# MCU.net
KiCad netlist of a schematic drawn in Altium Designer
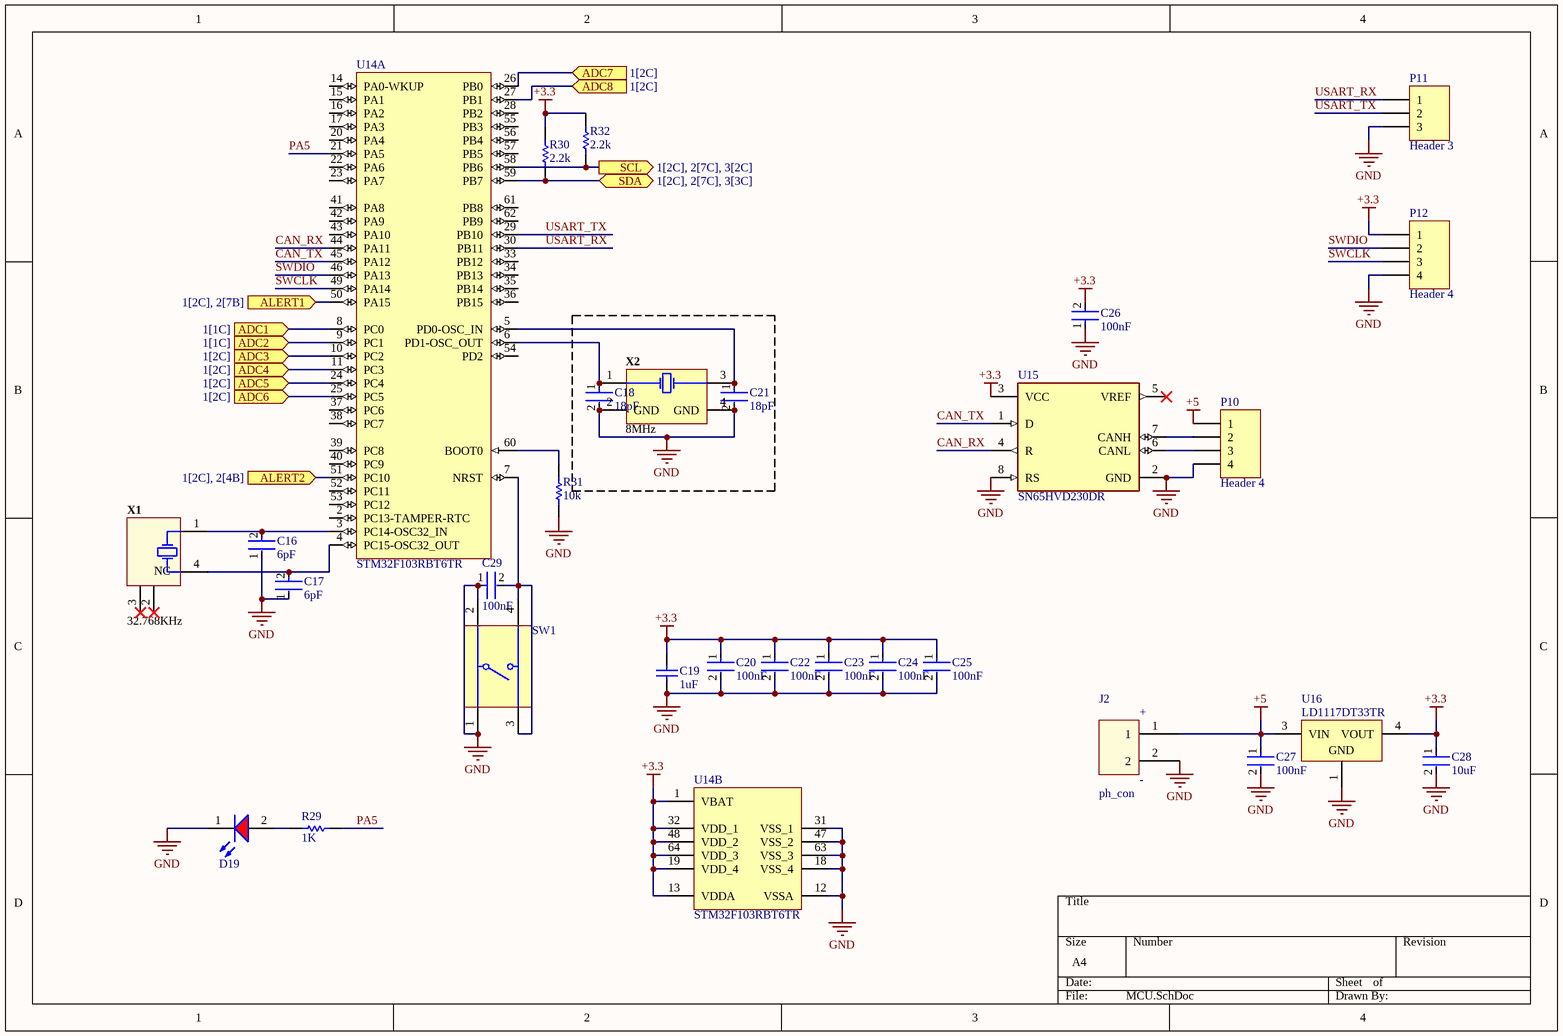
[diagram p0: MCU.SchDoc]

(export (version "E")
  (design (tool "Eeschema 10.0.6"))
  (components
    (comp (ref "C16")
      (value "6pF")
      (footprint "FP-C1608-080-0_1-IPC_C")
      (description "Multilayer Ceramic Capacitors 6pF ±0.25pF 50V C0G SMD 0603")
      (libsource (lib "Altium Content Vault") (part "236180d848d6139a670b325ea6854c9"))
    )
    (comp (ref "C17")
      (value "6pF")
      (footprint "FP-C1608-080-0_1-IPC_C")
      (description "Multilayer Ceramic Capacitors 6pF ±0.25pF 50V C0G SMD 0603")
      (libsource (lib "Altium Content Vault") (part "236180d848d6139a670b325ea6854c9"))
    )
    (comp (ref "C18")
      (value "18pF")
      (footprint "FP-C0603C-CF-MFG")
      (description "CAP CER 18PF 100V 5% NP0 0603")
      (fields (field (name "TOLERANCE") "0.05") (field (name "MANUFACTURER") "KEMET"))
      (libsource (lib "Altium Content Vault") (part "b4654b650e69147ec39a6b967a45e02"))
    )
    (comp (ref "C19")
      (value "1uF")
      (footprint "CAPC2013X145X50LL20T25")
      (fields (field (name "MANUFACTURER") "Kemet") (field (name "PART NUMBER") "C0805C105K4PACTU"))
      (libsource (lib "Altium Content Vault") (part "CAP"))
    )
    (comp (ref "C20")
      (value "100nF")
      (footprint "FP-0805-L_2_01_0_2-W_1_25-IPC_B")
      (description "General Purpose Ceramic Capacitor, 0805, 100nF, 10%, X7R, 15%, 100V")
      (fields (field (name "VOLTAGE") "100V") (field (name "TOLERANCE") "10%"))
      (libsource (lib "Altium Content Vault") (part "b4654b650e69147ec39a6b967a45e02"))
    )
    (comp (ref "C21")
      (value "18pF")
      (footprint "FP-C0603C-CF-MFG")
      (description "CAP CER 18PF 100V 5% NP0 0603")
      (fields (field (name "TOLERANCE") "0.05") (field (name "MANUFACTURER") "KEMET"))
      (libsource (lib "Altium Content Vault") (part "b4654b650e69147ec39a6b967a45e02"))
    )
    (comp (ref "C22")
      (value "100nF")
      (footprint "FP-0805-L_2_01_0_2-W_1_25-IPC_B")
      (description "General Purpose Ceramic Capacitor, 0805, 100nF, 10%, X7R, 15%, 100V")
      (fields (field (name "VOLTAGE") "100V") (field (name "TOLERANCE") "10%"))
      (libsource (lib "Altium Content Vault") (part "b4654b650e69147ec39a6b967a45e02"))
    )
    (comp (ref "C23")
      (value "100nF")
      (footprint "FP-0805-L_2_01_0_2-W_1_25-IPC_B")
      (description "General Purpose Ceramic Capacitor, 0805, 100nF, 10%, X7R, 15%, 100V")
      (fields (field (name "VOLTAGE") "100V") (field (name "TOLERANCE") "10%"))
      (libsource (lib "Altium Content Vault") (part "b4654b650e69147ec39a6b967a45e02"))
    )
    (comp (ref "C24")
      (value "100nF")
      (footprint "FP-0805-L_2_01_0_2-W_1_25-IPC_B")
      (description "General Purpose Ceramic Capacitor, 0805, 100nF, 10%, X7R, 15%, 100V")
      (fields (field (name "VOLTAGE") "100V") (field (name "TOLERANCE") "10%"))
      (libsource (lib "Altium Content Vault") (part "b4654b650e69147ec39a6b967a45e02"))
    )
    (comp (ref "C25")
      (value "100nF")
      (footprint "FP-0805-L_2_01_0_2-W_1_25-IPC_B")
      (description "General Purpose Ceramic Capacitor, 0805, 100nF, 10%, X7R, 15%, 100V")
      (fields (field (name "VOLTAGE") "100V") (field (name "TOLERANCE") "10%"))
      (libsource (lib "Altium Content Vault") (part "b4654b650e69147ec39a6b967a45e02"))
    )
    (comp (ref "C26")
      (value "100nF")
      (footprint "FP-0805-L_2_01_0_2-W_1_25-IPC_B")
      (description "General Purpose Ceramic Capacitor, 0805, 100nF, 10%, X7R, 15%, 100V")
      (fields (field (name "VOLTAGE") "100V") (field (name "TOLERANCE") "10%"))
      (libsource (lib "Altium Content Vault") (part "b4654b650e69147ec39a6b967a45e02"))
    )
    (comp (ref "C27")
      (value "100nF")
      (footprint "FP-0805-L_2_01_0_2-W_1_25-IPC_B")
      (description "General Purpose Ceramic Capacitor, 0805, 100nF, 10%, X7R, 15%, 100V")
      (fields (field (name "VOLTAGE") "100V") (field (name "TOLERANCE") "10%"))
      (libsource (lib "Altium Content Vault") (part "b4654b650e69147ec39a6b967a45e02"))
    )
    (comp (ref "C28")
      (value "10uF")
      (footprint "FP-C0805C-DG-IPC_B")
      (description "CAP CER 10UF 10V X5R 0805")
      (fields (field (name "TOLERANCE") "10%") (field (name "MANUFACTURER PART NUMBER") "C0805C106K8PACTU"))
      (libsource (lib "Altium Content Vault") (part "11868f565c42a9108669ba33697ecf6"))
    )
    (comp (ref "C29")
      (value "100nF")
      (footprint "FP-0805-L_2_01_0_2-W_1_25-IPC_B")
      (description "General Purpose Ceramic Capacitor, 0805, 100nF, 10%, X7R, 15%, 100V")
      (fields (field (name "VOLTAGE") "100V") (field (name "TOLERANCE") "10%"))
      (libsource (lib "Altium Content Vault") (part "b4654b650e69147ec39a6b967a45e02"))
    )
    (comp (ref "D19")
      (value "150080SS75000")
      (footprint "WL-SMCW_0805_150080xx75000")
      (libsource (lib "Altium Content Vault") (part "LED_Red_2A-1K"))
    )
    (comp (ref "J2")
      (value "ph_con")
      (footprint "Phoenix")
      (libsource (lib "XT+PHOENIX") (part "Connector_2"))
    )
    (comp (ref "P10")
      (value "Header 4")
      (footprint "HDR1X4")
      (description "Header, 4-Pin")
      (fields (field (name "PUBLISHER") "Altium Limited"))
      (libsource (lib "Miscellaneous Connectors") (part "Header 4"))
    )
    (comp (ref "P11")
      (value "Header 3")
      (footprint "HDR1X3")
      (description "Header, 3-Pin")
      (fields (field (name "PUBLISHER") "Altium Limited"))
      (libsource (lib "Miscellaneous Connectors") (part "Header 3"))
    )
    (comp (ref "P12")
      (value "Header 4")
      (footprint "HDR1X4")
      (description "Header, 4-Pin")
      (fields (field (name "PUBLISHER") "Altium Limited"))
      (libsource (lib "Miscellaneous Connectors") (part "Header 4"))
    )
    (comp (ref "R29")
      (value "1K")
      (footprint "RESC2013X60X35ML10T20")
      (description "Chip Resistor, 1 KOhm, +/- 1%, 125 mW, -55 to 155 degC, 0805 (2012 Metric), RoHS, Tape and Reel")
      (fields (field (name "TOLERANCE") "1%") (field (name "MANUFACTURER") "Yageo"))
      (libsource (lib "Altium Content Vault") (part "RES-2"))
    )
    (comp (ref "R30")
      (value "2.2k")
      (footprint "RESC2013X60X35ML10T20")
      (fields (field (name "TOLERANCE") "5%") (field (name "MANUFACTURER") "Yageo"))
      (libsource (lib "Altium Content Vault") (part "RES-2"))
    )
    (comp (ref "R31")
      (value "10k")
      (footprint "RESC2013X60X35ML10T20")
      (fields (field (name "TOLERANCE") "5%") (field (name "MANUFACTURER") "Yageo"))
      (libsource (lib "Altium Content Vault") (part "RES-2"))
    )
    (comp (ref "R32")
      (value "2.2k")
      (footprint "RESC2013X60X35ML10T20")
      (fields (field (name "TOLERANCE") "5%") (field (name "MANUFACTURER") "Yageo"))
      (libsource (lib "Altium Content Vault") (part "RES-2"))
    )
    (comp (ref "SW1")
      (value "PTS525SM10SMTRLFS")
      (footprint "CKCP-PTS525SM10SMTR-4_V")
      (description "Microminiature Tact Switch, SPST-NO, 50 mA, 12 VDC, -40 to 60 degC, 4-Pin SMD, RoHS, Tape and Reel")
      (fields (field (name "MANUFACTURER") "C&K Components"))
      (libsource (lib "Altium Content Vault") (part "SW-SPST-4_A"))
    )
    (comp (ref "U14")
      (value "STM32F103RBT6TR")
      (footprint "STM-LQFP64_V")
      (libsource (lib "Altium Content Vault") (part "MC-ARM-STM32F103X8_B-SQ64"))
    )
    (comp (ref "U15")
      (value "SN65HVD230DR")
      (footprint "FP-D0008A-IPC_A")
      (description "IC TRANSCEIVER HALF 1/1 8SOIC")
      (libsource (lib "Altium Content Vault") (part "43b56812b1adf0e60a7acfb7c27ab91"))
    )
    (comp (ref "U16")
      (value "LD1117DT33TR")
      (footprint "TO-252_M")
      (description "Fixed Low Drop Positive Voltage Regulator, 3.3V, 3-Pin DPAK, Tape and Reel")
      (libsource (lib "Altium Content Vault") (part "PM-REG-LD1117-SOT3"))
    )
    (comp (ref "X1")
      (value "32.768KHz")
      (footprint "ABRA-ABS25-4_V")
      (fields (field (name "TOLERANCE") "20PPM") (field (name "MANUFACTURER") "Abracon"))
      (libsource (lib "Altium Content Vault") (part "ABRA-XTAL_1-4-4"))
    )
    (comp (ref "X2")
      (value "8MHz")
      (footprint "TXC-7B-4_V")
      (description "SMD Seam Sealing Crystal, 8 MHz, +/- 30 ppm, 18 pF, -10 to 70 degC, 4-Pin SMD, RoHS, Tape and Reel")
      (fields (field (name "TOLERANCE") "1%"))
      (libsource (lib "Altium Content Vault") (part "XTAL-1-3-4"))
    )
  )
  (nets
    (net (code "1") (name "+3.3") (class "Default")
      (node (ref "C19") (pin "2") (pinfunction "2_2") (pintype "passive"))
      (node (ref "C20") (pin "1") (pinfunction "1_1") (pintype "passive"))
      (node (ref "C22") (pin "1") (pinfunction "1_1") (pintype "passive"))
      (node (ref "C23") (pin "1") (pinfunction "1_1") (pintype "passive"))
      (node (ref "C24") (pin "1") (pinfunction "1_1") (pintype "passive"))
      (node (ref "C25") (pin "1") (pinfunction "1_1") (pintype "passive"))
      (node (ref "C26") (pin "2") (pinfunction "2_2") (pintype "passive"))
      (node (ref "C28") (pin "1") (pinfunction "1_1") (pintype "passive"))
      (node (ref "P12") (pin "1") (pinfunction "1_1") (pintype "passive"))
      (node (ref "R30") (pin "2") (pinfunction "2_2") (pintype "passive"))
      (node (ref "R32") (pin "2") (pinfunction "2_2") (pintype "passive"))
      (node (ref "U14") (pin "1") (pinfunction "VBAT_1") (pintype "power_in"))
      (node (ref "U14") (pin "13") (pinfunction "VDDA_13") (pintype "power_in"))
      (node (ref "U14") (pin "19") (pinfunction "VDD_4_19") (pintype "power_in"))
      (node (ref "U14") (pin "32") (pinfunction "VDD_1_32") (pintype "power_in"))
      (node (ref "U14") (pin "48") (pinfunction "VDD_2_48") (pintype "power_in"))
      (node (ref "U14") (pin "64") (pinfunction "VDD_3_64") (pintype "power_in"))
      (node (ref "U15") (pin "3") (pinfunction "VCC_3") (pintype "power_in"))
      (node (ref "U16") (pin "4") (pinfunction "VOUT_4") (pintype "power_in"))
    )
    (net (code "2") (name "+5") (class "Default")
      (node (ref "C27") (pin "1") (pinfunction "1_1") (pintype "passive"))
      (node (ref "J2") (pin "1") (pinfunction "1_1") (pintype "passive"))
      (node (ref "P10") (pin "1") (pinfunction "1_1") (pintype "passive"))
      (node (ref "U16") (pin "3") (pinfunction "VIN_3") (pintype "power_in"))
    )
    (net (code "3") (name "/ADC1") (class "Default")
      (node (ref "U14") (pin "8") (pinfunction "PC0_8") (pintype "bidirectional"))
    )
    (net (code "4") (name "/ADC2") (class "Default")
      (node (ref "U14") (pin "9") (pinfunction "PC1_9") (pintype "bidirectional"))
    )
    (net (code "5") (name "/ADC3") (class "Default")
      (node (ref "U14") (pin "10") (pinfunction "PC2_10") (pintype "bidirectional"))
    )
    (net (code "6") (name "/ADC4") (class "Default")
      (node (ref "U14") (pin "11") (pinfunction "PC3_11") (pintype "bidirectional"))
    )
    (net (code "7") (name "/ADC5") (class "Default")
      (node (ref "U14") (pin "24") (pinfunction "PC4_24") (pintype "bidirectional"))
    )
    (net (code "8") (name "/ADC6") (class "Default")
      (node (ref "U14") (pin "25") (pinfunction "PC5_25") (pintype "bidirectional"))
    )
    (net (code "9") (name "/ADC7") (class "Default")
      (node (ref "U14") (pin "26") (pinfunction "PB0_26") (pintype "bidirectional"))
    )
    (net (code "10") (name "/ADC8") (class "Default")
      (node (ref "U14") (pin "27") (pinfunction "PB1_27") (pintype "bidirectional"))
    )
    (net (code "11") (name "/ALERT1") (class "Default")
      (node (ref "U14") (pin "50") (pinfunction "PA15_50") (pintype "bidirectional"))
    )
    (net (code "12") (name "/ALERT2") (class "Default")
      (node (ref "U14") (pin "51") (pinfunction "PC10_51") (pintype "bidirectional"))
    )
    (net (code "13") (name "/CAN_RX") (class "Default")
      (node (ref "U14") (pin "44") (pinfunction "PA11_44") (pintype "bidirectional"))
      (node (ref "U15") (pin "4") (pinfunction "R_4") (pintype "output"))
    )
    (net (code "14") (name "/CAN_TX") (class "Default")
      (node (ref "U14") (pin "45") (pinfunction "PA12_45") (pintype "bidirectional"))
      (node (ref "U15") (pin "1") (pinfunction "D_1") (pintype "input"))
    )
    (net (code "15") (name "/PA5") (class "Default")
      (node (ref "R29") (pin "1") (pinfunction "1_1") (pintype "passive"))
      (node (ref "U14") (pin "21") (pinfunction "PA5_21") (pintype "bidirectional"))
    )
    (net (code "16") (name "/SCL") (class "Default")
      (node (ref "R32") (pin "1") (pinfunction "1_1") (pintype "passive"))
      (node (ref "U14") (pin "58") (pinfunction "PB6_58") (pintype "bidirectional"))
    )
    (net (code "17") (name "/SDA") (class "Default")
      (node (ref "R30") (pin "1") (pinfunction "1_1") (pintype "passive"))
      (node (ref "U14") (pin "59") (pinfunction "PB7_59") (pintype "bidirectional"))
    )
    (net (code "18") (name "/SWCLK") (class "Default")
      (node (ref "P12") (pin "3") (pinfunction "3_3") (pintype "passive"))
      (node (ref "U14") (pin "49") (pinfunction "PA14_49") (pintype "bidirectional"))
    )
    (net (code "19") (name "/SWDIO") (class "Default")
      (node (ref "P12") (pin "2") (pinfunction "2_2") (pintype "passive"))
      (node (ref "U14") (pin "46") (pinfunction "PA13_46") (pintype "bidirectional"))
    )
    (net (code "20") (name "/USART_RX") (class "Default")
      (node (ref "P11") (pin "1") (pinfunction "1_1") (pintype "passive"))
      (node (ref "U14") (pin "30") (pinfunction "PB11_30") (pintype "bidirectional"))
    )
    (net (code "21") (name "/USART_TX") (class "Default")
      (node (ref "P11") (pin "2") (pinfunction "2_2") (pintype "passive"))
      (node (ref "U14") (pin "29") (pinfunction "PB10_29") (pintype "bidirectional"))
    )
    (net (code "22") (name "GND") (class "Default")
      (node (ref "C16") (pin "1") (pinfunction "1_1") (pintype "passive"))
      (node (ref "C17") (pin "1") (pinfunction "1_1") (pintype "passive"))
      (node (ref "C18") (pin "2") (pinfunction "2_2") (pintype "passive"))
      (node (ref "C19") (pin "1") (pinfunction "1_1") (pintype "passive"))
      (node (ref "C20") (pin "2") (pinfunction "2_2") (pintype "passive"))
      (node (ref "C21") (pin "2") (pinfunction "2_2") (pintype "passive"))
      (node (ref "C22") (pin "2") (pinfunction "2_2") (pintype "passive"))
      (node (ref "C23") (pin "2") (pinfunction "2_2") (pintype "passive"))
      (node (ref "C24") (pin "2") (pinfunction "2_2") (pintype "passive"))
      (node (ref "C25") (pin "2") (pinfunction "2_2") (pintype "passive"))
      (node (ref "C26") (pin "1") (pinfunction "1_1") (pintype "passive"))
      (node (ref "C27") (pin "2") (pinfunction "2_2") (pintype "passive"))
      (node (ref "C28") (pin "2") (pinfunction "2_2") (pintype "passive"))
      (node (ref "C29") (pin "1") (pinfunction "1_1") (pintype "passive"))
      (node (ref "D19") (pin "1") (pinfunction "K_1") (pintype "passive"))
      (node (ref "J2") (pin "2") (pinfunction "2_2") (pintype "passive"))
      (node (ref "P10") (pin "4") (pinfunction "4_4") (pintype "passive"))
      (node (ref "P11") (pin "3") (pinfunction "3_3") (pintype "passive"))
      (node (ref "P12") (pin "4") (pinfunction "4_4") (pintype "passive"))
      (node (ref "R31") (pin "1") (pinfunction "1_1") (pintype "passive"))
      (node (ref "SW1") (pin "1") (pinfunction "1_1") (pintype "passive"))
      (node (ref "SW1") (pin "2") (pinfunction "2_2") (pintype "passive"))
      (node (ref "U14") (pin "12") (pinfunction "VSSA_12") (pintype "power_in"))
      (node (ref "U14") (pin "18") (pinfunction "VSS_4_18") (pintype "power_in"))
      (node (ref "U14") (pin "31") (pinfunction "VSS_1_31") (pintype "power_in"))
      (node (ref "U14") (pin "47") (pinfunction "VSS_2_47") (pintype "power_in"))
      (node (ref "U14") (pin "63") (pinfunction "VSS_3_63") (pintype "power_in"))
      (node (ref "U15") (pin "2") (pinfunction "GND_2") (pintype "power_in"))
      (node (ref "U15") (pin "8") (pinfunction "RS_8") (pintype "input"))
      (node (ref "U16") (pin "1") (pinfunction "GND_1") (pintype "power_in"))
      (node (ref "X2") (pin "2") (pinfunction "GND_2") (pintype "power_in"))
      (node (ref "X2") (pin "4") (pinfunction "GND_4") (pintype "power_in"))
    )
    (net (code "23") (name "Net-(D19-A)") (class "Default")
      (node (ref "D19") (pin "2") (pinfunction "A_2") (pintype "passive"))
      (node (ref "R29") (pin "2") (pinfunction "2_2") (pintype "passive"))
    )
    (net (code "24") (name "Net-(U14A-BOOT0)") (class "Default")
      (node (ref "R31") (pin "2") (pinfunction "2_2") (pintype "passive"))
      (node (ref "U14") (pin "60") (pinfunction "BOOT0_60") (pintype "input"))
    )
    (net (code "25") (name "Net-(U14A-NRST)") (class "Default")
      (node (ref "C29") (pin "2") (pinfunction "2_2") (pintype "passive"))
      (node (ref "SW1") (pin "3") (pinfunction "3_3") (pintype "passive"))
      (node (ref "SW1") (pin "4") (pinfunction "4_4") (pintype "passive"))
      (node (ref "U14") (pin "7") (pinfunction "NRST_7") (pintype "bidirectional"))
    )
    (net (code "26") (name "Net-(U14A-PC14-OSC32_IN)") (class "Default")
      (node (ref "C16") (pin "2") (pinfunction "2_2") (pintype "passive"))
      (node (ref "U14") (pin "3") (pinfunction "PC14-OSC32_IN_3") (pintype "bidirectional"))
      (node (ref "X1") (pin "1") (pinfunction "X1_1") (pintype "passive"))
    )
    (net (code "27") (name "Net-(U14A-PC15-OSC32_OUT)") (class "Default")
      (node (ref "C17") (pin "2") (pinfunction "2_2") (pintype "passive"))
      (node (ref "U14") (pin "4") (pinfunction "PC15-OSC32_OUT_4") (pintype "bidirectional"))
      (node (ref "X1") (pin "4") (pinfunction "X2_4") (pintype "passive"))
    )
    (net (code "28") (name "Net-(U14A-PD0-OSC_IN)") (class "Default")
      (node (ref "C21") (pin "1") (pinfunction "1_1") (pintype "passive"))
      (node (ref "U14") (pin "5") (pinfunction "PD0-OSC_IN_5") (pintype "bidirectional"))
      (node (ref "X2") (pin "3") (pinfunction "X2_3") (pintype "passive"))
    )
    (net (code "29") (name "Net-(U14A-PD1-OSC_OUT)") (class "Default")
      (node (ref "C18") (pin "1") (pinfunction "1_1") (pintype "passive"))
      (node (ref "U14") (pin "6") (pinfunction "PD1-OSC_OUT_6") (pintype "bidirectional"))
      (node (ref "X2") (pin "1") (pinfunction "X1_1") (pintype "passive"))
    )
    (net (code "30") (name "Net-(U15-CANH)") (class "Default")
      (node (ref "P10") (pin "2") (pinfunction "2_2") (pintype "passive"))
      (node (ref "U15") (pin "7") (pinfunction "CANH_7") (pintype "bidirectional"))
    )
    (net (code "31") (name "Net-(U15-CANL)") (class "Default")
      (node (ref "P10") (pin "3") (pinfunction "3_3") (pintype "passive"))
      (node (ref "U15") (pin "6") (pinfunction "CANL_6") (pintype "bidirectional"))
    )
    (net (code "32") (name "unconnected-(U14A-PA0-WKUP-Pad14)") (class "Default")
      (node (ref "U14") (pin "14") (pinfunction "PA0-WKUP_14") (pintype "bidirectional"))
    )
    (net (code "33") (name "unconnected-(U14A-PA1-Pad15)") (class "Default")
      (node (ref "U14") (pin "15") (pinfunction "PA1_15") (pintype "bidirectional"))
    )
    (net (code "34") (name "unconnected-(U14A-PA2-Pad16)") (class "Default")
      (node (ref "U14") (pin "16") (pinfunction "PA2_16") (pintype "bidirectional"))
    )
    (net (code "35") (name "unconnected-(U14A-PA3-Pad17)") (class "Default")
      (node (ref "U14") (pin "17") (pinfunction "PA3_17") (pintype "bidirectional"))
    )
    (net (code "36") (name "unconnected-(U14A-PA4-Pad20)") (class "Default")
      (node (ref "U14") (pin "20") (pinfunction "PA4_20") (pintype "bidirectional"))
    )
    (net (code "37") (name "unconnected-(U14A-PA6-Pad22)") (class "Default")
      (node (ref "U14") (pin "22") (pinfunction "PA6_22") (pintype "bidirectional"))
    )
    (net (code "38") (name "unconnected-(U14A-PA7-Pad23)") (class "Default")
      (node (ref "U14") (pin "23") (pinfunction "PA7_23") (pintype "bidirectional"))
    )
    (net (code "39") (name "unconnected-(U14A-PA8-Pad41)") (class "Default")
      (node (ref "U14") (pin "41") (pinfunction "PA8_41") (pintype "bidirectional"))
    )
    (net (code "40") (name "unconnected-(U14A-PA9-Pad42)") (class "Default")
      (node (ref "U14") (pin "42") (pinfunction "PA9_42") (pintype "bidirectional"))
    )
    (net (code "41") (name "unconnected-(U14A-PA10-Pad43)") (class "Default")
      (node (ref "U14") (pin "43") (pinfunction "PA10_43") (pintype "bidirectional"))
    )
    (net (code "42") (name "unconnected-(U14A-PB2-Pad28)") (class "Default")
      (node (ref "U14") (pin "28") (pinfunction "PB2_28") (pintype "bidirectional"))
    )
    (net (code "43") (name "unconnected-(U14A-PB3-Pad55)") (class "Default")
      (node (ref "U14") (pin "55") (pinfunction "PB3_55") (pintype "bidirectional"))
    )
    (net (code "44") (name "unconnected-(U14A-PB4-Pad56)") (class "Default")
      (node (ref "U14") (pin "56") (pinfunction "PB4_56") (pintype "bidirectional"))
    )
    (net (code "45") (name "unconnected-(U14A-PB5-Pad57)") (class "Default")
      (node (ref "U14") (pin "57") (pinfunction "PB5_57") (pintype "bidirectional"))
    )
    (net (code "46") (name "unconnected-(U14A-PB8-Pad61)") (class "Default")
      (node (ref "U14") (pin "61") (pinfunction "PB8_61") (pintype "bidirectional"))
    )
    (net (code "47") (name "unconnected-(U14A-PB9-Pad62)") (class "Default")
      (node (ref "U14") (pin "62") (pinfunction "PB9_62") (pintype "bidirectional"))
    )
    (net (code "48") (name "unconnected-(U14A-PB12-Pad33)") (class "Default")
      (node (ref "U14") (pin "33") (pinfunction "PB12_33") (pintype "bidirectional"))
    )
    (net (code "49") (name "unconnected-(U14A-PB13-Pad34)") (class "Default")
      (node (ref "U14") (pin "34") (pinfunction "PB13_34") (pintype "bidirectional"))
    )
    (net (code "50") (name "unconnected-(U14A-PB14-Pad35)") (class "Default")
      (node (ref "U14") (pin "35") (pinfunction "PB14_35") (pintype "bidirectional"))
    )
    (net (code "51") (name "unconnected-(U14A-PB15-Pad36)") (class "Default")
      (node (ref "U14") (pin "36") (pinfunction "PB15_36") (pintype "bidirectional"))
    )
    (net (code "52") (name "unconnected-(U14A-PC6-Pad37)") (class "Default")
      (node (ref "U14") (pin "37") (pinfunction "PC6_37") (pintype "bidirectional"))
    )
    (net (code "53") (name "unconnected-(U14A-PC7-Pad38)") (class "Default")
      (node (ref "U14") (pin "38") (pinfunction "PC7_38") (pintype "bidirectional"))
    )
    (net (code "54") (name "unconnected-(U14A-PC8-Pad39)") (class "Default")
      (node (ref "U14") (pin "39") (pinfunction "PC8_39") (pintype "bidirectional"))
    )
    (net (code "55") (name "unconnected-(U14A-PC9-Pad40)") (class "Default")
      (node (ref "U14") (pin "40") (pinfunction "PC9_40") (pintype "bidirectional"))
    )
    (net (code "56") (name "unconnected-(U14A-PC11-Pad52)") (class "Default")
      (node (ref "U14") (pin "52") (pinfunction "PC11_52") (pintype "bidirectional"))
    )
    (net (code "57") (name "unconnected-(U14A-PC12-Pad53)") (class "Default")
      (node (ref "U14") (pin "53") (pinfunction "PC12_53") (pintype "bidirectional"))
    )
    (net (code "58") (name "unconnected-(U14A-PC13-TAMPER-RTC-Pad2)") (class "Default")
      (node (ref "U14") (pin "2") (pinfunction "PC13-TAMPER-RTC_2") (pintype "bidirectional"))
    )
    (net (code "59") (name "unconnected-(U14A-PD2-Pad54)") (class "Default")
      (node (ref "U14") (pin "54") (pinfunction "PD2_54") (pintype "bidirectional"))
    )
    (net (code "60") (name "unconnected-(U15-VREF-Pad5)") (class "Default")
      (node (ref "U15") (pin "5") (pinfunction "VREF_5") (pintype "output+no_connect"))
    )
    (net (code "61") (name "unconnected-(X1-NC-Pad2)") (class "Default")
      (node (ref "X1") (pin "2") (pinfunction "NC_2") (pintype "passive+no_connect"))
    )
    (net (code "62") (name "unconnected-(X1-NC-Pad3)") (class "Default")
      (node (ref "X1") (pin "3") (pinfunction "NC_3") (pintype "passive+no_connect"))
    )
  )
)
